# power_shield.net
KiCad netlist of a schematic drawn in EAGLE
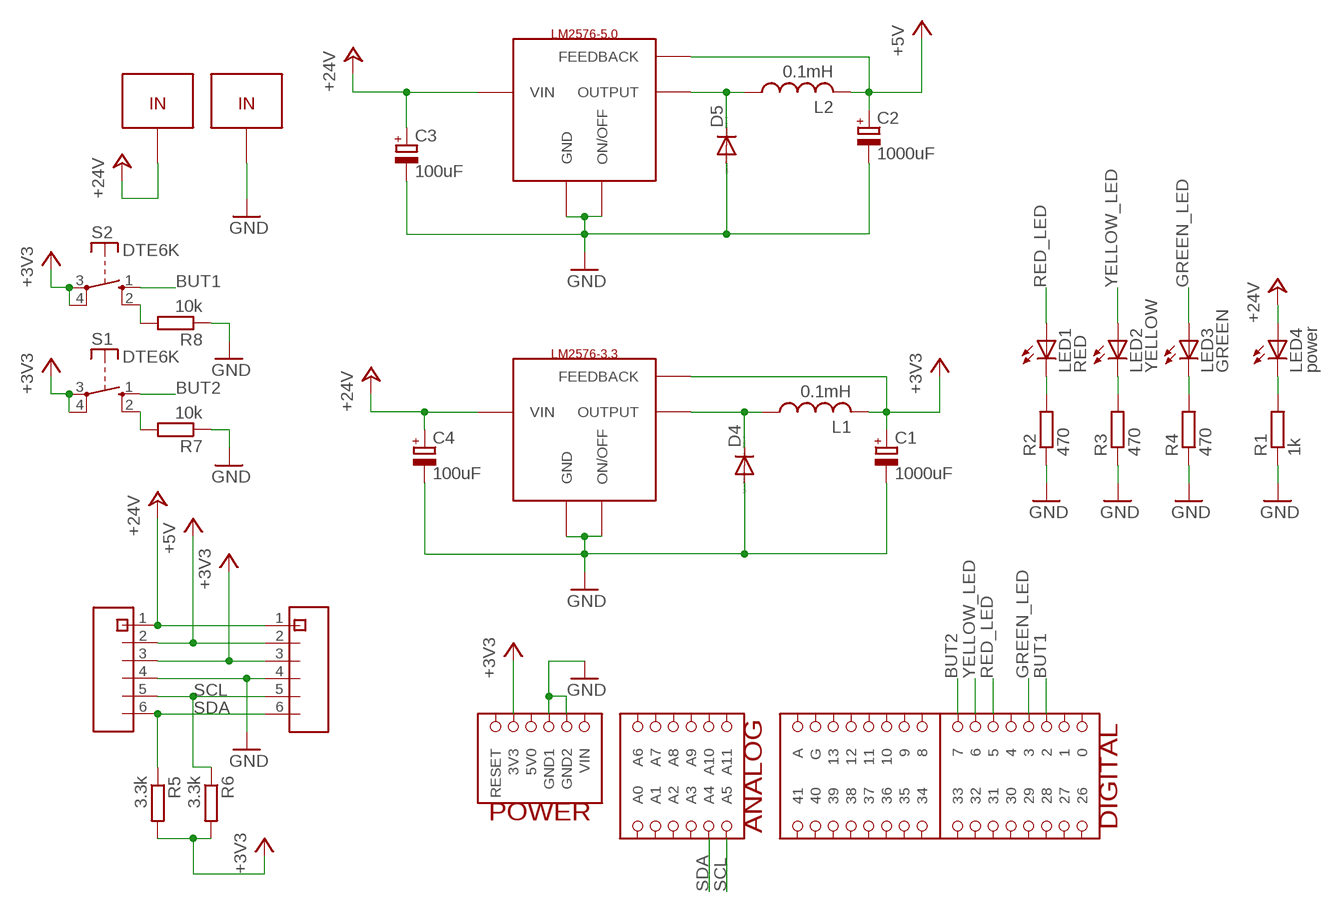
[diagram p0: schematic, sheet 1]

(export (version "E")
  (design (tool "Eeschema 10.0.6"))
  (components
    (comp (ref "C1")
      (value "1000uF")
      (footprint "eagle-import:150CLZ-1010")
      (libsource (lib "eagle-import") (part "CPOL-EU150CLZ-1010"))
    )
    (comp (ref "C2")
      (value "1000uF")
      (footprint "eagle-import:150CLZ-1010")
      (libsource (lib "eagle-import") (part "CPOL-EU150CLZ-1010"))
    )
    (comp (ref "C3")
      (value "100uF")
      (footprint "eagle-import:150CLZ-1010")
      (libsource (lib "eagle-import") (part "CPOL-EU150CLZ-1010"))
    )
    (comp (ref "C4")
      (value "100uF")
      (footprint "eagle-import:150CLZ-1010")
      (libsource (lib "eagle-import") (part "CPOL-EU150CLZ-1010"))
    )
    (comp (ref "D4")
      (value "DIODE-DO214AA")
      (footprint "eagle-import:DO214AA")
      (libsource (lib "eagle-import") (part "DIODE-DO214AA"))
    )
    (comp (ref "D5")
      (value "DIODE-DO214AA")
      (footprint "eagle-import:DO214AA")
      (libsource (lib "eagle-import") (part "DIODE-DO214AA"))
    )
    (comp (ref "L1")
      (value "0.1mH")
      (footprint "eagle-import:6000-XXXX-RC")
      (libsource (lib "eagle-import") (part "L-US6000-XXX-RC"))
    )
    (comp (ref "L2")
      (value "0.1mH")
      (footprint "eagle-import:6000-XXXX-RC")
      (libsource (lib "eagle-import") (part "L-US6000-XXX-RC"))
    )
    (comp (ref "LED1")
      (value "RED")
      (footprint "eagle-import:CHIPLED_1206")
      (libsource (lib "eagle-import") (part "LEDCHIPLED_1206"))
    )
    (comp (ref "LED2")
      (value "YELLOW")
      (footprint "eagle-import:CHIPLED_1206")
      (libsource (lib "eagle-import") (part "LEDCHIPLED_1206"))
    )
    (comp (ref "LED3")
      (value "GREEN")
      (footprint "eagle-import:CHIPLED_1206")
      (libsource (lib "eagle-import") (part "LEDCHIPLED_1206"))
    )
    (comp (ref "LED4")
      (value "power")
      (footprint "eagle-import:CHIPLED_1206")
      (libsource (lib "eagle-import") (part "LEDCHIPLED_1206"))
    )
    (comp (ref "R1")
      (value "1k")
      (footprint "eagle-import:R0603")
      (libsource (lib "eagle-import") (part "R-EU_R0603"))
    )
    (comp (ref "R2")
      (value "470")
      (footprint "eagle-import:R0603")
      (libsource (lib "eagle-import") (part "R-EU_R0603"))
    )
    (comp (ref "R3")
      (value "470")
      (footprint "eagle-import:R0603")
      (libsource (lib "eagle-import") (part "R-EU_R0603"))
    )
    (comp (ref "R4")
      (value "470")
      (footprint "eagle-import:R0603")
      (libsource (lib "eagle-import") (part "R-EU_R0603"))
    )
    (comp (ref "R5")
      (value "3.3k")
      (footprint "eagle-import:R0603")
      (libsource (lib "eagle-import") (part "R-EU_R0603"))
    )
    (comp (ref "R6")
      (value "3.3k")
      (footprint "eagle-import:R0603")
      (libsource (lib "eagle-import") (part "R-EU_R0603"))
    )
    (comp (ref "R7")
      (value "10k")
      (footprint "eagle-import:R0603")
      (libsource (lib "eagle-import") (part "R-EU_R0603"))
    )
    (comp (ref "R8")
      (value "10k")
      (footprint "eagle-import:R0603")
      (libsource (lib "eagle-import") (part "R-EU_R0603"))
    )
    (comp (ref "S1")
      (value "DTE6K")
      (footprint "eagle-import:DTE6K")
      (libsource (lib "eagle-import") (part "DTE6K"))
    )
    (comp (ref "S2")
      (value "DTE6K")
      (footprint "eagle-import:DTE6K")
      (libsource (lib "eagle-import") (part "DTE6K"))
    )
    (comp (ref "U$1")
      (value "UNO32_SHIELD")
      (footprint "eagle-import:UNO32_SHIELD")
      (libsource (lib "eagle-import") (part "UNO32_SHIELD"))
    )
    (comp (ref "U$2")
      (value "LM2576-5.0")
      (footprint "eagle-import:TO-220-5")
      (libsource (lib "eagle-import") (part "LM2576-5.0"))
    )
    (comp (ref "U$3")
      (value "LM2576-3.3")
      (footprint "eagle-import:TO-220-5")
      (libsource (lib "eagle-import") (part "LM2576-3.3"))
    )
    (comp (ref "U$4")
      (value "MOLEX_3.96MM_6P")
      (footprint "eagle-import:MOLEX_3.96MM_6P")
      (libsource (lib "eagle-import") (part "MOLEX_3.96MM_6P"))
    )
    (comp (ref "U$5")
      (value "MOLEX_3.96MM_6P")
      (footprint "eagle-import:MOLEX_3.96MM_6P")
      (libsource (lib "eagle-import") (part "MOLEX_3.96MM_6P"))
    )
    (comp (ref "U$6")
      (value "LABBHYLSA")
      (footprint "eagle-import:LABBHYLSA")
      (libsource (lib "eagle-import") (part "LABBHYLSA"))
    )
    (comp (ref "U$7")
      (value "LABBHYLSA")
      (footprint "eagle-import:LABBHYLSA")
      (libsource (lib "eagle-import") (part "LABBHYLSA"))
    )
  )
  (nets
    (net (code "1") (name "+3V3") (class "Default")
      (node (ref "C1") (pin "+") (pinfunction "+_+") (pintype "passive"))
      (node (ref "L1") (pin "2") (pinfunction "2_2") (pintype "passive"))
      (node (ref "R5") (pin "2") (pinfunction "2_2") (pintype "passive"))
      (node (ref "R6") (pin "2") (pinfunction "2_2") (pintype "passive"))
      (node (ref "S1") (pin "3") (pinfunction "P_3") (pintype "passive"))
      (node (ref "S1") (pin "4") (pinfunction "P_4") (pintype "passive"))
      (node (ref "S2") (pin "3") (pinfunction "P_3") (pintype "passive"))
      (node (ref "S2") (pin "4") (pinfunction "P_4") (pintype "passive"))
      (node (ref "U$1") (pin "3V3") (pinfunction "3V3_3V3") (pintype "bidirectional"))
      (node (ref "U$3") (pin "4") (pinfunction "FEEDBACK_4") (pintype "bidirectional"))
      (node (ref "U$4") (pin "3") (pinfunction "3_3") (pintype "bidirectional"))
      (node (ref "U$5") (pin "3") (pinfunction "3_3") (pintype "bidirectional"))
    )
    (net (code "2") (name "+5V") (class "Default")
      (node (ref "C2") (pin "+") (pinfunction "+_+") (pintype "passive"))
      (node (ref "L2") (pin "2") (pinfunction "2_2") (pintype "passive"))
      (node (ref "U$2") (pin "4") (pinfunction "FEEDBACK_4") (pintype "bidirectional"))
      (node (ref "U$4") (pin "2") (pinfunction "2_2") (pintype "bidirectional"))
      (node (ref "U$5") (pin "2") (pinfunction "2_2") (pintype "bidirectional"))
    )
    (net (code "3") (name "+24V") (class "Default")
      (node (ref "C3") (pin "+") (pinfunction "+_+") (pintype "passive"))
      (node (ref "C4") (pin "+") (pinfunction "+_+") (pintype "passive"))
      (node (ref "LED4") (pin "A") (pinfunction "A_A") (pintype "passive"))
      (node (ref "U$2") (pin "1") (pinfunction "VIN_1") (pintype "bidirectional"))
      (node (ref "U$3") (pin "1") (pinfunction "VIN_1") (pintype "bidirectional"))
      (node (ref "U$4") (pin "1") (pinfunction "1_1") (pintype "bidirectional"))
      (node (ref "U$5") (pin "1") (pinfunction "1_1") (pintype "bidirectional"))
      (node (ref "U$6") (pin "IN") (pinfunction "IN_IN") (pintype "bidirectional"))
      (node (ref "U$6") (pin "IN2") (pinfunction "IN_IN2") (pintype "bidirectional"))
    )
    (net (code "4") (name "/BUT1") (class "Default")
      (node (ref "S2") (pin "1") (pinfunction "S_1") (pintype "passive"))
      (node (ref "U$1") (pin "2") (pinfunction "2_2") (pintype "bidirectional"))
    )
    (net (code "5") (name "/BUT2") (class "Default")
      (node (ref "S1") (pin "1") (pinfunction "S_1") (pintype "passive"))
      (node (ref "U$1") (pin "7") (pinfunction "7_7") (pintype "bidirectional"))
    )
    (net (code "6") (name "/GREEN_LED") (class "Default")
      (node (ref "LED3") (pin "A") (pinfunction "A_A") (pintype "passive"))
      (node (ref "U$1") (pin "3") (pinfunction "3_3") (pintype "bidirectional"))
    )
    (net (code "7") (name "/RED_LED") (class "Default")
      (node (ref "LED1") (pin "A") (pinfunction "A_A") (pintype "passive"))
      (node (ref "U$1") (pin "5") (pinfunction "5_5") (pintype "bidirectional"))
    )
    (net (code "8") (name "/SCL") (class "Default")
      (node (ref "R6") (pin "1") (pinfunction "1_1") (pintype "passive"))
      (node (ref "U$1") (pin "A5") (pinfunction "A5_A5") (pintype "bidirectional"))
      (node (ref "U$4") (pin "5") (pinfunction "5_5") (pintype "bidirectional"))
      (node (ref "U$5") (pin "5") (pinfunction "5_5") (pintype "bidirectional"))
    )
    (net (code "9") (name "/SDA") (class "Default")
      (node (ref "R5") (pin "1") (pinfunction "1_1") (pintype "passive"))
      (node (ref "U$1") (pin "A4") (pinfunction "A4_A4") (pintype "bidirectional"))
      (node (ref "U$4") (pin "6") (pinfunction "6_6") (pintype "bidirectional"))
      (node (ref "U$5") (pin "6") (pinfunction "6_6") (pintype "bidirectional"))
    )
    (net (code "10") (name "/YELLOW_LED") (class "Default")
      (node (ref "LED2") (pin "A") (pinfunction "A_A") (pintype "passive"))
      (node (ref "U$1") (pin "6") (pinfunction "6_6") (pintype "bidirectional"))
    )
    (net (code "11") (name "GND") (class "Default")
      (node (ref "C1") (pin "-") (pinfunction "-_-") (pintype "passive"))
      (node (ref "C2") (pin "-") (pinfunction "-_-") (pintype "passive"))
      (node (ref "C3") (pin "-") (pinfunction "-_-") (pintype "passive"))
      (node (ref "C4") (pin "-") (pinfunction "-_-") (pintype "passive"))
      (node (ref "D4") (pin "A") (pinfunction "A_A") (pintype "passive"))
      (node (ref "D5") (pin "A") (pinfunction "A_A") (pintype "passive"))
      (node (ref "R1") (pin "1") (pinfunction "1_1") (pintype "passive"))
      (node (ref "R2") (pin "1") (pinfunction "1_1") (pintype "passive"))
      (node (ref "R3") (pin "1") (pinfunction "1_1") (pintype "passive"))
      (node (ref "R4") (pin "1") (pinfunction "1_1") (pintype "passive"))
      (node (ref "R7") (pin "1") (pinfunction "1_1") (pintype "passive"))
      (node (ref "R8") (pin "1") (pinfunction "1_1") (pintype "passive"))
      (node (ref "U$1") (pin "GND1") (pinfunction "GND1_GND1") (pintype "bidirectional"))
      (node (ref "U$1") (pin "GND2") (pinfunction "GND2_GND2") (pintype "bidirectional"))
      (node (ref "U$2") (pin "3") (pinfunction "GND_3") (pintype "bidirectional"))
      (node (ref "U$2") (pin "5") (pinfunction "ON/OFF_5") (pintype "bidirectional"))
      (node (ref "U$3") (pin "3") (pinfunction "GND_3") (pintype "bidirectional"))
      (node (ref "U$3") (pin "5") (pinfunction "ON/OFF_5") (pintype "bidirectional"))
      (node (ref "U$4") (pin "4") (pinfunction "4_4") (pintype "bidirectional"))
      (node (ref "U$5") (pin "4") (pinfunction "4_4") (pintype "bidirectional"))
      (node (ref "U$7") (pin "IN") (pinfunction "IN_IN") (pintype "bidirectional"))
      (node (ref "U$7") (pin "IN2") (pinfunction "IN_IN2") (pintype "bidirectional"))
    )
    (net (code "12") (name "Net-(LED1-PadC)") (class "Default")
      (node (ref "LED1") (pin "C") (pinfunction "C_C") (pintype "passive"))
      (node (ref "R2") (pin "2") (pinfunction "2_2") (pintype "passive"))
    )
    (net (code "13") (name "Net-(LED2-PadC)") (class "Default")
      (node (ref "LED2") (pin "C") (pinfunction "C_C") (pintype "passive"))
      (node (ref "R3") (pin "2") (pinfunction "2_2") (pintype "passive"))
    )
    (net (code "14") (name "Net-(LED3-PadC)") (class "Default")
      (node (ref "LED3") (pin "C") (pinfunction "C_C") (pintype "passive"))
      (node (ref "R4") (pin "2") (pinfunction "2_2") (pintype "passive"))
    )
    (net (code "15") (name "Net-(LED4-PadC)") (class "Default")
      (node (ref "LED4") (pin "C") (pinfunction "C_C") (pintype "passive"))
      (node (ref "R1") (pin "2") (pinfunction "2_2") (pintype "passive"))
    )
    (net (code "16") (name "Net-(R7-Pad2)") (class "Default")
      (node (ref "R7") (pin "2") (pinfunction "2_2") (pintype "passive"))
      (node (ref "S1") (pin "2") (pinfunction "S_2") (pintype "passive"))
    )
    (net (code "17") (name "Net-(R8-Pad2)") (class "Default")
      (node (ref "R8") (pin "2") (pinfunction "2_2") (pintype "passive"))
      (node (ref "S2") (pin "2") (pinfunction "S_2") (pintype "passive"))
    )
    (net (code "18") (name "Net-(U$2-OUTPUT)") (class "Default")
      (node (ref "D5") (pin "C") (pinfunction "C_C") (pintype "passive"))
      (node (ref "L2") (pin "1") (pinfunction "1_1") (pintype "passive"))
      (node (ref "U$2") (pin "2") (pinfunction "OUTPUT_2") (pintype "bidirectional"))
    )
    (net (code "19") (name "Net-(U$3-OUTPUT)") (class "Default")
      (node (ref "D4") (pin "C") (pinfunction "C_C") (pintype "passive"))
      (node (ref "L1") (pin "1") (pinfunction "1_1") (pintype "passive"))
      (node (ref "U$3") (pin "2") (pinfunction "OUTPUT_2") (pintype "bidirectional"))
    )
    (net (code "20") (name "unconnected-(U$1-Pad0)") (class "Default")
      (node (ref "U$1") (pin "0") (pinfunction "0_0") (pintype "bidirectional"))
    )
    (net (code "21") (name "unconnected-(U$1-Pad1)") (class "Default")
      (node (ref "U$1") (pin "1") (pinfunction "1_1") (pintype "bidirectional"))
    )
    (net (code "22") (name "unconnected-(U$1-Pad4)") (class "Default")
      (node (ref "U$1") (pin "4") (pinfunction "4_4") (pintype "bidirectional"))
    )
    (net (code "23") (name "unconnected-(U$1-Pad5V0)") (class "Default")
      (node (ref "U$1") (pin "5V0") (pinfunction "5V0_5V0") (pintype "bidirectional"))
    )
    (net (code "24") (name "unconnected-(U$1-Pad8)") (class "Default")
      (node (ref "U$1") (pin "8") (pinfunction "8_8") (pintype "bidirectional"))
    )
    (net (code "25") (name "unconnected-(U$1-Pad9)") (class "Default")
      (node (ref "U$1") (pin "9") (pinfunction "9_9") (pintype "bidirectional"))
    )
    (net (code "26") (name "unconnected-(U$1-Pad10)") (class "Default")
      (node (ref "U$1") (pin "10") (pinfunction "10_10") (pintype "bidirectional"))
    )
    (net (code "27") (name "unconnected-(U$1-Pad11)") (class "Default")
      (node (ref "U$1") (pin "11") (pinfunction "11_11") (pintype "bidirectional"))
    )
    (net (code "28") (name "unconnected-(U$1-Pad12)") (class "Default")
      (node (ref "U$1") (pin "12") (pinfunction "12_12") (pintype "bidirectional"))
    )
    (net (code "29") (name "unconnected-(U$1-Pad13)") (class "Default")
      (node (ref "U$1") (pin "13") (pinfunction "13_13") (pintype "bidirectional"))
    )
    (net (code "30") (name "unconnected-(U$1-Pad26)") (class "Default")
      (node (ref "U$1") (pin "26") (pinfunction "26_26") (pintype "bidirectional"))
    )
    (net (code "31") (name "unconnected-(U$1-Pad27)") (class "Default")
      (node (ref "U$1") (pin "27") (pinfunction "27_27") (pintype "bidirectional"))
    )
    (net (code "32") (name "unconnected-(U$1-Pad28)") (class "Default")
      (node (ref "U$1") (pin "28") (pinfunction "28_28") (pintype "bidirectional"))
    )
    (net (code "33") (name "unconnected-(U$1-Pad29)") (class "Default")
      (node (ref "U$1") (pin "29") (pinfunction "29_29") (pintype "bidirectional"))
    )
    (net (code "34") (name "unconnected-(U$1-Pad30)") (class "Default")
      (node (ref "U$1") (pin "30") (pinfunction "30_30") (pintype "bidirectional"))
    )
    (net (code "35") (name "unconnected-(U$1-Pad31)") (class "Default")
      (node (ref "U$1") (pin "31") (pinfunction "31_31") (pintype "bidirectional"))
    )
    (net (code "36") (name "unconnected-(U$1-Pad32)") (class "Default")
      (node (ref "U$1") (pin "32") (pinfunction "32_32") (pintype "bidirectional"))
    )
    (net (code "37") (name "unconnected-(U$1-Pad33)") (class "Default")
      (node (ref "U$1") (pin "33") (pinfunction "33_33") (pintype "bidirectional"))
    )
    (net (code "38") (name "unconnected-(U$1-Pad34)") (class "Default")
      (node (ref "U$1") (pin "34") (pinfunction "34_34") (pintype "bidirectional"))
    )
    (net (code "39") (name "unconnected-(U$1-Pad35)") (class "Default")
      (node (ref "U$1") (pin "35") (pinfunction "35_35") (pintype "bidirectional"))
    )
    (net (code "40") (name "unconnected-(U$1-Pad36)") (class "Default")
      (node (ref "U$1") (pin "36") (pinfunction "36_36") (pintype "bidirectional"))
    )
    (net (code "41") (name "unconnected-(U$1-Pad37)") (class "Default")
      (node (ref "U$1") (pin "37") (pinfunction "37_37") (pintype "bidirectional"))
    )
    (net (code "42") (name "unconnected-(U$1-Pad38)") (class "Default")
      (node (ref "U$1") (pin "38") (pinfunction "38_38") (pintype "bidirectional"))
    )
    (net (code "43") (name "unconnected-(U$1-Pad39)") (class "Default")
      (node (ref "U$1") (pin "39") (pinfunction "39_39") (pintype "bidirectional"))
    )
    (net (code "44") (name "unconnected-(U$1-Pad40)") (class "Default")
      (node (ref "U$1") (pin "40") (pinfunction "40_40") (pintype "bidirectional"))
    )
    (net (code "45") (name "unconnected-(U$1-Pad41)") (class "Default")
      (node (ref "U$1") (pin "41") (pinfunction "41_41") (pintype "bidirectional"))
    )
    (net (code "46") (name "unconnected-(U$1-PadA)") (class "Default")
      (node (ref "U$1") (pin "A") (pinfunction "A_A") (pintype "bidirectional"))
    )
    (net (code "47") (name "unconnected-(U$1-PadA0)") (class "Default")
      (node (ref "U$1") (pin "A0") (pinfunction "A0_A0") (pintype "bidirectional"))
    )
    (net (code "48") (name "unconnected-(U$1-PadA1)") (class "Default")
      (node (ref "U$1") (pin "A1") (pinfunction "A1_A1") (pintype "bidirectional"))
    )
    (net (code "49") (name "unconnected-(U$1-PadA2)") (class "Default")
      (node (ref "U$1") (pin "A2") (pinfunction "A2_A2") (pintype "bidirectional"))
    )
    (net (code "50") (name "unconnected-(U$1-PadA3)") (class "Default")
      (node (ref "U$1") (pin "A3") (pinfunction "A3_A3") (pintype "bidirectional"))
    )
    (net (code "51") (name "unconnected-(U$1-PadA6)") (class "Default")
      (node (ref "U$1") (pin "A6") (pinfunction "A6_A6") (pintype "bidirectional"))
    )
    (net (code "52") (name "unconnected-(U$1-PadA7)") (class "Default")
      (node (ref "U$1") (pin "A7") (pinfunction "A7_A7") (pintype "bidirectional"))
    )
    (net (code "53") (name "unconnected-(U$1-PadA8)") (class "Default")
      (node (ref "U$1") (pin "A8") (pinfunction "A8_A8") (pintype "bidirectional"))
    )
    (net (code "54") (name "unconnected-(U$1-PadA9)") (class "Default")
      (node (ref "U$1") (pin "A9") (pinfunction "A9_A9") (pintype "bidirectional"))
    )
    (net (code "55") (name "unconnected-(U$1-PadA10)") (class "Default")
      (node (ref "U$1") (pin "A10") (pinfunction "A10_A10") (pintype "bidirectional"))
    )
    (net (code "56") (name "unconnected-(U$1-PadA11)") (class "Default")
      (node (ref "U$1") (pin "A11") (pinfunction "A11_A11") (pintype "bidirectional"))
    )
    (net (code "57") (name "unconnected-(U$1-PadG)") (class "Default")
      (node (ref "U$1") (pin "G") (pinfunction "G_G") (pintype "bidirectional"))
    )
    (net (code "58") (name "unconnected-(U$1-PadRESET)") (class "Default")
      (node (ref "U$1") (pin "RESET") (pinfunction "RESET_RESET") (pintype "bidirectional"))
    )
    (net (code "59") (name "unconnected-(U$1-PadVIN)") (class "Default")
      (node (ref "U$1") (pin "VIN") (pinfunction "VIN_VIN") (pintype "bidirectional"))
    )
  )
)
